# EasyEDA_SCH_Elproj_PCB_2023-05-11.net
KiCad netlist of a schematic drawn in EasyEDA
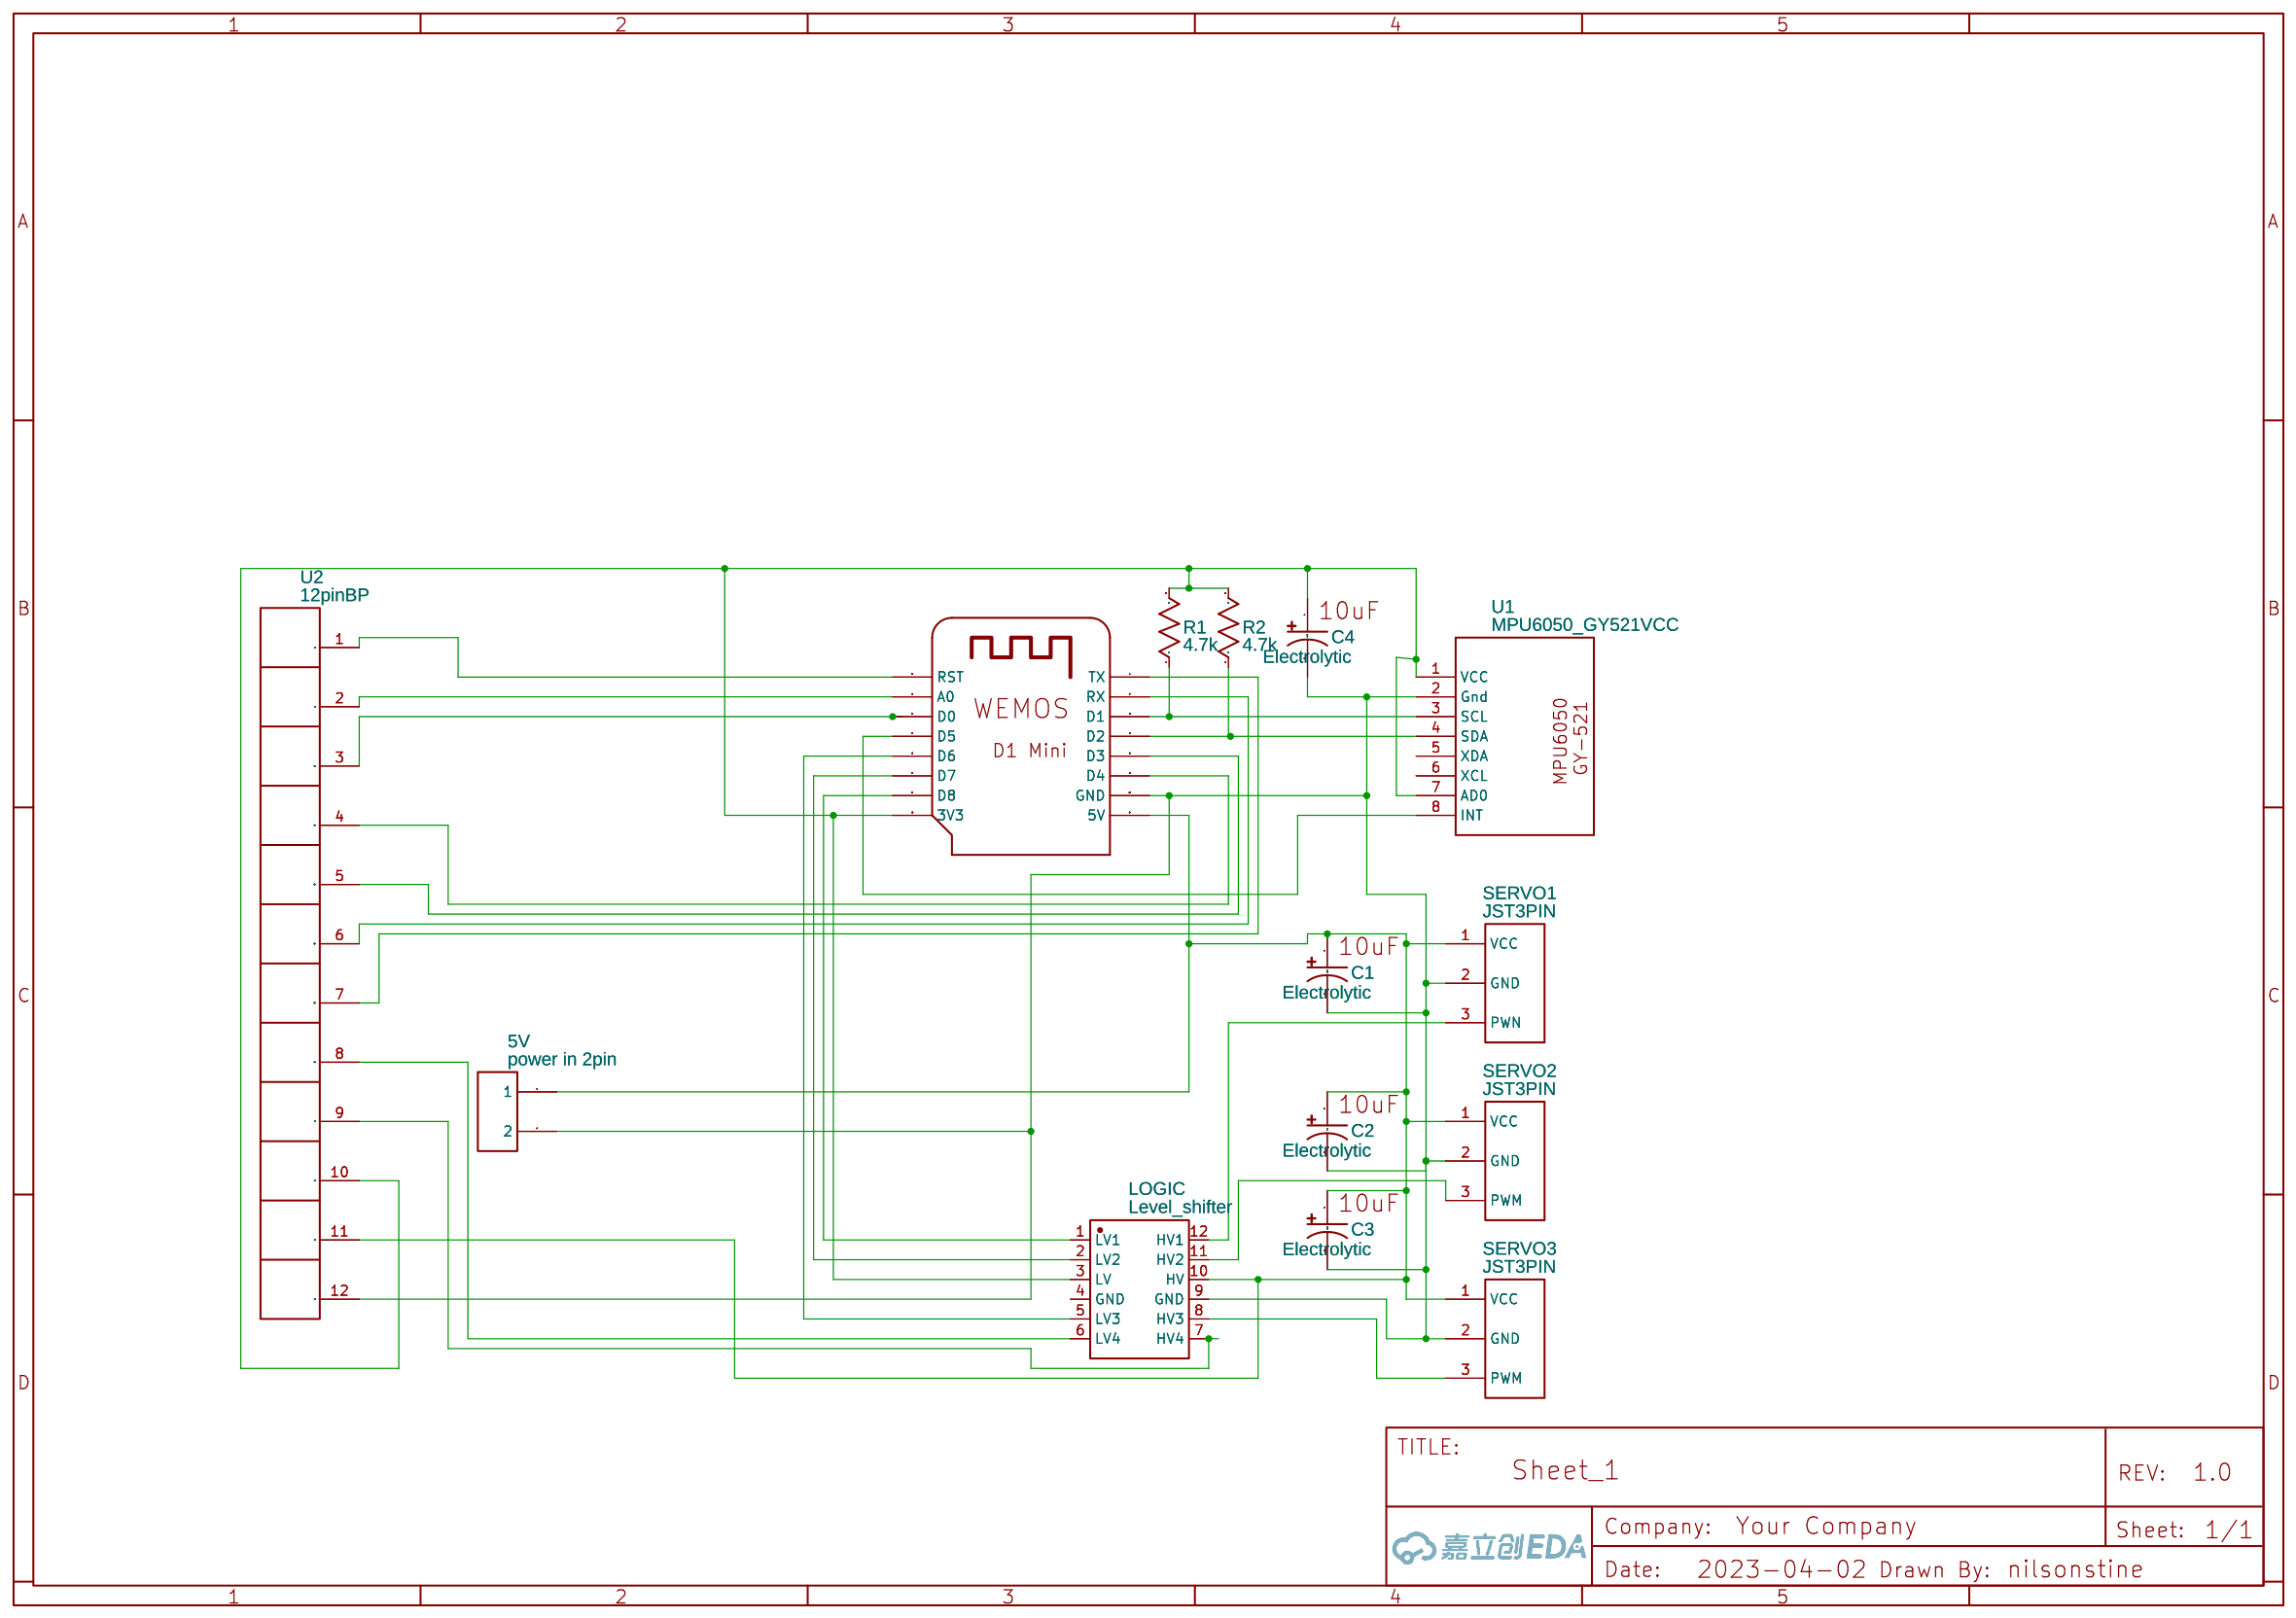
[diagram p0: schematic sheet]

(export (version "E")
  (design (tool "Eeschema 10.0.6"))
  (components
    (comp (ref "5V") (value "power in 2pin") (libsource (lib "") (part "terminal2pin")))
    (comp (ref "C1") (value "Electrolytic") (libsource (lib "") (part "CAPACITOR_ELECTROLYTIC_US_10UF")))
    (comp (ref "C2") (value "Electrolytic") (libsource (lib "") (part "CAPACITOR_ELECTROLYTIC_US_10UF_1")))
    (comp (ref "C3") (value "Electrolytic") (libsource (lib "") (part "CAPACITOR_ELECTROLYTIC_US_10UF_1")))
    (comp (ref "C4") (value "Electrolytic") (libsource (lib "") (part "CAPACITOR_ELECTROLYTIC_US_10UF")))
    (comp (ref "LOGIC") (value "Level_shifter") (libsource (lib "") (part "Level_shifter")))
    (comp (ref "R1") (value "4.7k") (libsource (lib "") (part "R_0603_US")))
    (comp (ref "R2") (value "4.7k") (libsource (lib "") (part "R_0603_US")))
    (comp (ref "SERVO1") (value "JST3PIN") (libsource (lib "") (part "JST3PIN_1")))
    (comp (ref "SERVO2") (value "JST3PIN") (libsource (lib "") (part "JST3PIN")))
    (comp (ref "SERVO3") (value "JST3PIN") (libsource (lib "") (part "JST3PIN")))
    (comp (ref "U1") (value "MPU6050_GY521VCC") (libsource (lib "") (part "MPU6050_GY521VCC")))
    (comp (ref "U2") (value "12pinBP") (libsource (lib "") (part "12pinBP")))
    (comp (ref "WEMOSU3") (value "WEMOS D1 Mini") (libsource (lib "") (part "Unknown_515_-440")))
  )
  (nets
    (net (code "1") (name "Net-(LOGIC-HV)") (class "Default")
      (node (ref "5V") (pin "1") (pinfunction "1_1") (pintype "unspecified"))
      (node (ref "C1") (pin "1") (pinfunction "1_1") (pintype "unspecified"))
      (node (ref "C2") (pin "1") (pinfunction "1_1") (pintype "unspecified"))
      (node (ref "C3") (pin "1") (pinfunction "1_1") (pintype "unspecified"))
      (node (ref "LOGIC") (pin "10") (pinfunction "HV_10") (pintype "unspecified"))
      (node (ref "SERVO1") (pin "1") (pinfunction "VCC_1") (pintype "unspecified"))
      (node (ref "SERVO2") (pin "1") (pinfunction "VCC_1") (pintype "unspecified"))
      (node (ref "SERVO3") (pin "1") (pinfunction "VCC_1") (pintype "unspecified"))
      (node (ref "U2") (pin "11") (pinfunction "+5V_11") (pintype "unspecified"))
      (node (ref "WEMOSU3") (pin "5V") (pinfunction "5V_5V") (pintype "unspecified"))
    )
    (net (code "2") (name "Net-(LOGIC-HV1)") (class "Default")
      (node (ref "LOGIC") (pin "12") (pinfunction "HV1_12") (pintype "unspecified"))
      (node (ref "SERVO1") (pin "3") (pinfunction "PWN_3") (pintype "unspecified"))
    )
    (net (code "3") (name "Net-(LOGIC-HV2)") (class "Default")
      (node (ref "LOGIC") (pin "11") (pinfunction "HV2_11") (pintype "unspecified"))
      (node (ref "SERVO2") (pin "3") (pinfunction "PWM_3") (pintype "unspecified"))
    )
    (net (code "4") (name "Net-(LOGIC-HV3)") (class "Default")
      (node (ref "LOGIC") (pin "8") (pinfunction "HV3_8") (pintype "unspecified"))
      (node (ref "SERVO3") (pin "3") (pinfunction "PWM_3") (pintype "unspecified"))
    )
    (net (code "5") (name "Net-(LOGIC-HV4)") (class "Default")
      (node (ref "LOGIC") (pin "7") (pinfunction "HV4_7") (pintype "unspecified"))
      (node (ref "U2") (pin "9") (pinfunction "9_9") (pintype "unspecified"))
    )
    (net (code "6") (name "Net-(LOGIC-LV)") (class "Default")
      (node (ref "C4") (pin "1") (pinfunction "1_1") (pintype "unspecified"))
      (node (ref "LOGIC") (pin "3") (pinfunction "LV_3") (pintype "unspecified"))
      (node (ref "R1") (pin "2") (pinfunction "2_2") (pintype "unspecified"))
      (node (ref "R2") (pin "2") (pinfunction "2_2") (pintype "unspecified"))
      (node (ref "U1") (pin "1") (pinfunction "VCC_1") (pintype "unspecified"))
      (node (ref "U1") (pin "7") (pinfunction "AD0_7") (pintype "unspecified"))
      (node (ref "U2") (pin "10") (pinfunction "+5V_10") (pintype "unspecified"))
      (node (ref "WEMOSU3") (pin "3V3") (pinfunction "3V3_3V3") (pintype "unspecified"))
    )
    (net (code "7") (name "Net-(LOGIC-LV1)") (class "Default")
      (node (ref "LOGIC") (pin "1") (pinfunction "LV1_1") (pintype "unspecified"))
      (node (ref "WEMOSU3") (pin "D8") (pinfunction "D8_D8") (pintype "unspecified"))
    )
    (net (code "8") (name "Net-(LOGIC-LV2)") (class "Default")
      (node (ref "LOGIC") (pin "2") (pinfunction "LV2_2") (pintype "unspecified"))
      (node (ref "WEMOSU3") (pin "D7") (pinfunction "D7_D7") (pintype "unspecified"))
    )
    (net (code "9") (name "Net-(LOGIC-LV3)") (class "Default")
      (node (ref "LOGIC") (pin "5") (pinfunction "LV3_5") (pintype "unspecified"))
      (node (ref "WEMOSU3") (pin "D6") (pinfunction "D6_D6") (pintype "unspecified"))
    )
    (net (code "10") (name "Net-(LOGIC-LV4)") (class "Default")
      (node (ref "LOGIC") (pin "6") (pinfunction "LV4_6") (pintype "unspecified"))
      (node (ref "U2") (pin "8") (pinfunction "COM_8") (pintype "unspecified"))
    )
    (net (code "11") (name "Net-(SERVO1-GND)") (class "Default")
      (node (ref "5V") (pin "2") (pinfunction "2_2") (pintype "unspecified"))
      (node (ref "C1") (pin "2") (pinfunction "2_2") (pintype "unspecified"))
      (node (ref "C2") (pin "2") (pinfunction "2_2") (pintype "unspecified"))
      (node (ref "C3") (pin "2") (pinfunction "2_2") (pintype "unspecified"))
      (node (ref "C4") (pin "2") (pinfunction "2_2") (pintype "unspecified"))
      (node (ref "LOGIC") (pin "9") (pinfunction "GND_9") (pintype "unspecified"))
      (node (ref "SERVO1") (pin "2") (pinfunction "GND_2") (pintype "unspecified"))
      (node (ref "SERVO2") (pin "2") (pinfunction "GND_2") (pintype "unspecified"))
      (node (ref "SERVO3") (pin "2") (pinfunction "GND_2") (pintype "unspecified"))
      (node (ref "U1") (pin "2") (pinfunction "Gnd_2") (pintype "unspecified"))
      (node (ref "U2") (pin "12") (pinfunction "+5V_12") (pintype "unspecified"))
      (node (ref "WEMOSU3") (pin "GND") (pinfunction "GND_GND") (pintype "unspecified"))
    )
    (net (code "12") (name "Net-(U1-INT)") (class "Default")
      (node (ref "U1") (pin "8") (pinfunction "INT_8") (pintype "unspecified"))
      (node (ref "WEMOSU3") (pin "D5") (pinfunction "D5_D5") (pintype "unspecified"))
    )
    (net (code "13") (name "Net-(U1-SCL)") (class "Default")
      (node (ref "R1") (pin "1") (pinfunction "1_1") (pintype "unspecified"))
      (node (ref "U1") (pin "3") (pinfunction "SCL_3") (pintype "unspecified"))
      (node (ref "WEMOSU3") (pin "D1") (pinfunction "D1_D1") (pintype "unspecified"))
    )
    (net (code "14") (name "Net-(U1-SDA)") (class "Default")
      (node (ref "R2") (pin "1") (pinfunction "1_1") (pintype "unspecified"))
      (node (ref "U1") (pin "4") (pinfunction "SDA_4") (pintype "unspecified"))
      (node (ref "WEMOSU3") (pin "D2") (pinfunction "D2_D2") (pintype "unspecified"))
    )
    (net (code "15") (name "Net-(U2-+12V)") (class "Default")
      (node (ref "U2") (pin "3") (pinfunction "+12V_3") (pintype "unspecified"))
      (node (ref "WEMOSU3") (pin "D0") (pinfunction "D0_D0") (pintype "unspecified"))
    )
    (net (code "16") (name "Net-(U2--12V)") (class "Default")
      (node (ref "U2") (pin "4") (pinfunction "-12V_4") (pintype "unspecified"))
      (node (ref "WEMOSU3") (pin "D4") (pinfunction "D4_D4") (pintype "unspecified"))
    )
    (net (code "17") (name "Net-(U2-COM-Pad5)") (class "Default")
      (node (ref "U2") (pin "5") (pinfunction "COM_5") (pintype "unspecified"))
      (node (ref "WEMOSU3") (pin "D3") (pinfunction "D3_D3") (pintype "unspecified"))
    )
    (net (code "18") (name "Net-(U2-COM-Pad6)") (class "Default")
      (node (ref "U2") (pin "6") (pinfunction "COM_6") (pintype "unspecified"))
      (node (ref "WEMOSU3") (pin "RX") (pinfunction "RX_RX") (pintype "unspecified"))
    )
    (net (code "19") (name "Net-(U2-COM-Pad7)") (class "Default")
      (node (ref "U2") (pin "7") (pinfunction "COM_7") (pintype "unspecified"))
      (node (ref "WEMOSU3") (pin "TX") (pinfunction "TX_TX") (pintype "unspecified"))
    )
    (net (code "20") (name "Net-(U2-PG)") (class "Default")
      (node (ref "U2") (pin "1") (pinfunction "PG_1") (pintype "unspecified"))
      (node (ref "WEMOSU3") (pin "RST") (pinfunction "RST_RST") (pintype "unspecified"))
    )
    (net (code "21") (name "Net-(U2-Pad2)") (class "Default")
      (node (ref "U2") (pin "2") (pinfunction "2_2") (pintype "unspecified"))
      (node (ref "WEMOSU3") (pin "A0") (pinfunction "A0_A0") (pintype "unspecified"))
    )
    (net (code "22") (name "unconnected-(LOGIC-GND-Pad4)") (class "Default")
      (node (ref "LOGIC") (pin "4") (pinfunction "GND_4") (pintype "unspecified"))
    )
    (net (code "23") (name "unconnected-(U1-XCL-Pad6)") (class "Default")
      (node (ref "U1") (pin "6") (pinfunction "XCL_6") (pintype "unspecified"))
    )
    (net (code "24") (name "unconnected-(U1-XDA-Pad5)") (class "Default")
      (node (ref "U1") (pin "5") (pinfunction "XDA_5") (pintype "unspecified"))
    )
  )
)
